# AICat_V1_4.net
KiCad netlist of a schematic drawn in Altium Designer
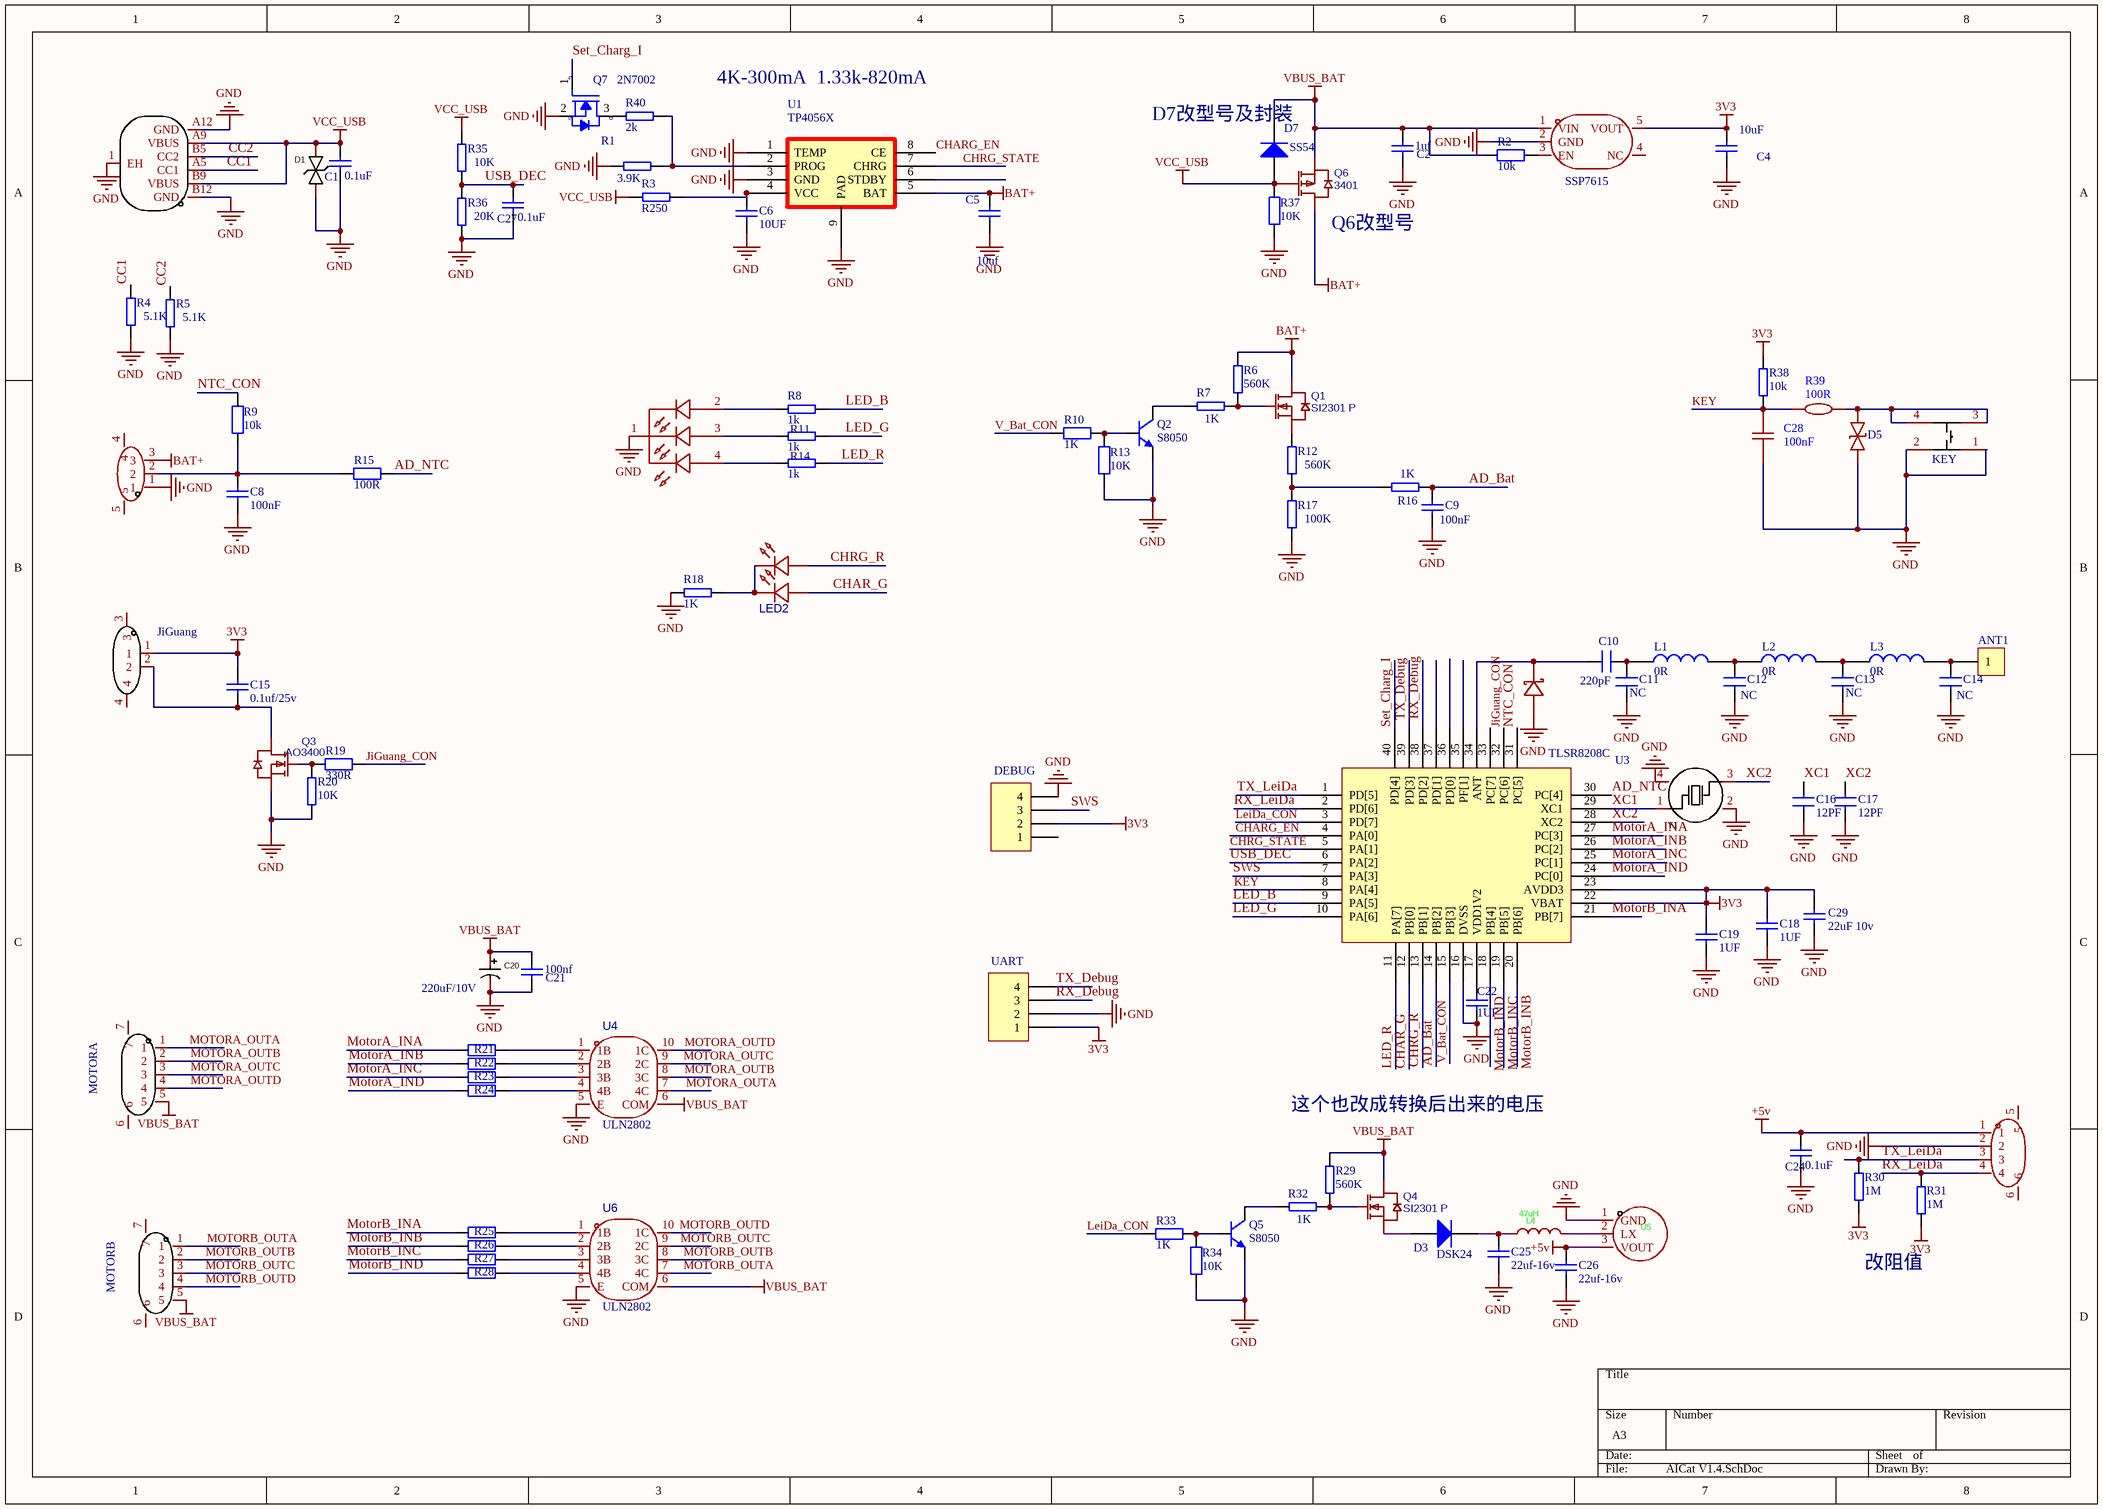
[diagram p0: AICat V1.4.SchDoc]

(export (version "E")
  (design (tool "Eeschema 10.0.6"))
  (components
    (comp (ref "ANT1")
      (value "~")
      (footprint "tp")
      (description "Connector")
      (libsource (lib "*") (part "CON1"))
    )
    (comp (ref "BAT1")
      (value "BX-PH2.0-3PWT")
      (footprint "HDR-TH_3P-P2.50_ZX-XH2.54-3PWZ")
      (libsource (lib "altium-import") (part "root_2_BX-PH2.0-3PWT_"))
    )
    (comp (ref "C1")
      (value "0.1uF")
      (footprint "0603_C")
      (description "Capacitor")
      (fields (field (name "PUBLISHER") "Altium Limited"))
      (libsource (lib "*") (part "Cap"))
    )
    (comp (ref "C2")
      (value "1uf")
      (footprint "0603_C")
      (description "无极电容")
      (libsource (lib "电容电阻电感保险") (part "Cap1"))
    )
    (comp (ref "C4")
      (value "10uF")
      (footprint "0603_C")
      (description "Capacitor")
      (fields (field (name "PUBLISHER") "Altium Limited"))
      (libsource (lib "*") (part "Cap"))
    )
    (comp (ref "C5")
      (value "10uf")
      (footprint "0603_C")
      (description "Capacitor")
      (fields (field (name "PUBLISHER") "Altium Limited"))
      (libsource (lib "*") (part "Cap"))
    )
    (comp (ref "C6") (value "10UF") (footprint "0603_c") (libsource (lib "DIY") (part "CAP")))
    (comp (ref "C8") (value "100nF") (footprint "0603_C") (libsource (lib "DIY") (part "CAP")))
    (comp (ref "C9") (value "100nF") (footprint "0603_C") (libsource (lib "DIY") (part "CAP")))
    (comp (ref "C10")
      (value "220pF")
      (footprint "0402_c")
      (description "Capacitor")
      (libsource (lib "*") (part "CAP"))
    )
    (comp (ref "C11")
      (value "NC")
      (footprint "0402_C")
      (description "Capacitor")
      (libsource (lib "*") (part "CAP"))
    )
    (comp (ref "C12")
      (value "NC")
      (footprint "0402_C")
      (description "Capacitor")
      (libsource (lib "*") (part "CAP"))
    )
    (comp (ref "C13")
      (value "NC")
      (footprint "0402_C")
      (description "Capacitor")
      (libsource (lib "*") (part "CAP"))
    )
    (comp (ref "C14")
      (value "NC")
      (footprint "0402_C")
      (description "Capacitor")
      (libsource (lib "*") (part "CAP"))
    )
    (comp (ref "C15")
      (value "0.1uf/25v")
      (footprint "0603_C")
      (description "Capacitor")
      (fields (field (name "PUBLISHER") "Altium Limited"))
      (libsource (lib "*") (part "Cap"))
    )
    (comp (ref "C16")
      (value "12PF")
      (footprint "0603_c")
      (description "Capacitor")
      (libsource (lib "*") (part "CAP"))
    )
    (comp (ref "C17")
      (value "12PF")
      (footprint "0603_c")
      (description "Capacitor")
      (libsource (lib "*") (part "CAP"))
    )
    (comp (ref "C18") (value "1UF") (footprint "0603_c") (libsource (lib "DIY") (part "CAP")))
    (comp (ref "C19") (value "1UF") (footprint "0603_c") (libsource (lib "DIY") (part "CAP")))
    (comp (ref "C20")
      (value "220uF/10V")
      (footprint "SMD 6.3*5.4 电解")
      (fields (field (name "MANUFACTURER PART") "RVT1A221M0605"))
      (libsource (lib "altium-import") (part "root_0_RVT1A221M0605_C72494_"))
    )
    (comp (ref "C21")
      (value "100nf")
      (footprint "0603_C")
      (description "无极电容")
      (libsource (lib "电容电阻电感保险") (part "Cap1"))
    )
    (comp (ref "C22") (value "1UF") (footprint "0603_c") (libsource (lib "DIY") (part "CAP")))
    (comp (ref "C24")
      (value "0.1uF")
      (footprint "0603_C")
      (description "Capacitor")
      (fields (field (name "PUBLISHER") "Altium Limited"))
      (libsource (lib "*") (part "Cap"))
    )
    (comp (ref "C25")
      (value "22uf-16v")
      (footprint "0805_c")
      (description "无极电容")
      (libsource (lib "电容电阻电感保险") (part "Cap1"))
    )
    (comp (ref "C26")
      (value "22uf-16v")
      (footprint "0805_c")
      (description "无极电容")
      (libsource (lib "电容电阻电感保险") (part "Cap1"))
    )
    (comp (ref "C27")
      (value "0.1uF")
      (footprint "0603_C")
      (description "Capacitor")
      (fields (field (name "PUBLISHER") "Altium Limited"))
      (libsource (lib "*") (part "Cap"))
    )
    (comp (ref "C28")
      (value "100nF")
      (footprint "0603_c")
      (libsource (lib "altium-import") (part "root_1_CAP_0603_"))
    )
    (comp (ref "C29")
      (value "22uF 10v")
      (footprint "0603_C")
      (description "Capacitor")
      (fields (field (name "PUBLISHER") "Altium Limited"))
      (libsource (lib "*") (part "Cap"))
    )
    (comp (ref "CN1")
      (value "JiGuang")
      (footprint "CONN-SMD_2P-P1.25-LT")
      (fields (field (name "MANUFACTURER PART") "HC-1.25-2PLT"))
      (libsource (lib "altium-import") (part "root_0_mirrored_HC-1.25-2PLT_"))
    )
    (comp (ref "CN2")
      (value "HC-1.25-4PLT")
      (footprint "CONN-SMD_4P-P1.25_LT")
      (libsource (lib "altium-import") (part "root_0_HC-1.25-4PLT_"))
    )
    (comp (ref "D1")
      (value "SMF5.0CA_C726939")
      (footprint "SOD-123 双向")
      (fields (field (name "MANUFACTURER PART") "SMF5.0CA"))
      (libsource (lib "altium-import") (part "root_1_SMF5.0CA_C726939_"))
    )
    (comp (ref "D2")
      (value "SE6V3LHN102T 6.3v单向")
      (footprint "0402-D")
      (libsource (lib "altium-import") (part "root_3_TPNSR05F20NXT5G_"))
    )
    (comp (ref "D3")
      (value "DSK24")
      (footprint "SOD-123FL")
      (description "High Conductance Fast Diode")
      (fields (field (name "PUBLISHER") "Altium Limited"))
      (libsource (lib "Miscellaneous Devices") (part "Diode 1N4148"))
    )
    (comp (ref "D5")
      (value "~")
      (footprint "SOD-523_L1.2-W0.8-LS1.6-RD")
      (fields (field (name "MANUFACTURER PART") "LESD5Z5.0CT1G"))
      (libsource (lib "altium-import") (part "root_1_LESD5Z5.0CT1G_"))
    )
    (comp (ref "D7")
      (value "SS54")
      (footprint "SMA")
      (description "High Conductance Fast Diode")
      (fields (field (name "PUBLISHER") "Altium Limited"))
      (libsource (lib "Miscellaneous Devices") (part "Diode 1N4148"))
    )
    (comp (ref "J1")
      (value "MOTORA")
      (footprint "CONN-SMD_1.25-5PLT")
      (fields (field (name "MANUFACTURER PART") "HC-1.25-5PLT"))
      (libsource (lib "altium-import") (part "root_0_mirrored_HC-1.25-5PLT_"))
    )
    (comp (ref "J2")
      (value "MOTORB")
      (footprint "CONN-SMD_1.25-5PLT")
      (fields (field (name "MANUFACTURER PART") "HC-1.25-5PLT"))
      (libsource (lib "altium-import") (part "root_0_mirrored_HC-1.25-5PLT_"))
    )
    (comp (ref "K1")
      (value "KEY")
      (footprint "KEY_SMD_4P")
      (fields (field (name "MANUFACTURER PART") "TS-1002S-05026C"))
      (libsource (lib "altium-import") (part "root_2_TS-1002S-05026C_"))
    )
    (comp (ref "L1") (value "0R") (footprint "0402_R") (libsource (lib "*") (part "INDUCTOR")))
    (comp (ref "L2") (value "0R") (footprint "0402_R") (libsource (lib "*") (part "INDUCTOR")))
    (comp (ref "L3") (value "0R") (footprint "0402_R") (libsource (lib "*") (part "INDUCTOR")))
    (comp (ref "L4")
      (value "47uH")
      (footprint "IND-SMD_L3.5-W3.0_CD31")
      (fields (field (name "MANUFACTURER PART") "CD31-470M 47UH"))
      (libsource (lib "altium-import") (part "root_0_CD31-470M 47UH_"))
    )
    (comp (ref "LED1")
      (value "XL-A3528RGBC-BM")
      (footprint "LED-ARRAY-SMD_4P-L3.2-W2.8-LS3.5-BL_XL-A3528RGBC-BM")
      (libsource (lib "altium-import") (part "root_2_XL-A3528RGBC-BM_"))
    )
    (comp (ref "LED2")
      (value "*")
      (footprint "LED-SMD_4P-L3.2-W1.6-TL_XL-3216SURUGC")
      (libsource (lib "altium-import") (part "root_0_TJ-S2012SW8TCGLC2R2G-A5_"))
    )
    (comp (ref "P1")
      (value "DEBUG")
      (footprint "SIP4-2.54")
      (description "Header, 4-Pin")
      (fields (field (name "PUBLISHER") "Altium Limited"))
      (libsource (lib "Miscellaneous Connectors") (part "Header 4"))
    )
    (comp (ref "P2")
      (value "UART")
      (footprint "SIP4-2.54")
      (description "Header, 4-Pin")
      (fields (field (name "PUBLISHER") "Altium Limited"))
      (libsource (lib "Miscellaneous Connectors") (part "Header 4"))
    )
    (comp (ref "Q1")
      (value "SI2301 P")
      (footprint "SOT-23")
      (fields
        (field (name "BOM_SUPPLIER PART") "C2890442")
        (field (name "BOM_MANUFACTURER PART") "JMTL3400A")
        (field (name "CONTRIBUTOR") "LCSC")
      )
      (libsource (lib "altium-import") (part "root_0_JMTL3400A_"))
    )
    (comp (ref "Q2")
      (value "S8050")
      (footprint "SOT-23(SOT-23-3)")
      (description "NPN三极管")
      (libsource (lib "二三极管mos可控硅") (part "NPN_sot23"))
    )
    (comp (ref "Q3")
      (value "AO3400")
      (footprint "SOT-23")
      (fields
        (field (name "BOM_SUPPLIER PART") "C2890442")
        (field (name "BOM_MANUFACTURER PART") "JMTL3400A")
        (field (name "CONTRIBUTOR") "LCSC")
      )
      (libsource (lib "altium-import") (part "root_0_mirrored_JMTL3400A_"))
    )
    (comp (ref "Q4")
      (value "SI2301 P")
      (footprint "SOT-23")
      (fields
        (field (name "BOM_SUPPLIER PART") "C2890442")
        (field (name "BOM_MANUFACTURER PART") "JMTL3400A")
        (field (name "CONTRIBUTOR") "LCSC")
      )
      (libsource (lib "altium-import") (part "root_0_JMTL3400A_"))
    )
    (comp (ref "Q5")
      (value "S8050")
      (footprint "SOT-23(SOT-23-3)")
      (description "NPN三极管")
      (libsource (lib "二三极管mos可控硅") (part "NPN_sot23"))
    )
    (comp (ref "Q6")
      (value "3401")
      (footprint "SOT-23")
      (fields (field (name "BOM_MANUFACTURER PART") "CJ3401") (field (name "BOM_SUPPLIER PART") "C13799"))
      (libsource (lib "altium-import") (part "root_2_mirrored_CJ3401_"))
    )
    (comp (ref "Q7") (value "2N7002") (footprint "SOT-23") (libsource (lib "*") (part "AO3400_SOT23")))
    (comp (ref "R1") (value "3.9K") (footprint "0603_R") (libsource (lib "DIY") (part "RES")))
    (comp (ref "R2")
      (value "10k")
      (footprint "0603_R")
      (description "Resistor")
      (fields (field (name "PUBLISHER") "Altium Limited"))
      (libsource (lib "") (part "Res2_2"))
    )
    (comp (ref "R3") (value "R250") (footprint "1206_R") (libsource (lib "DIY") (part "RES")))
    (comp (ref "R4") (value "5.1K") (footprint "0603_R") (libsource (lib "DIY") (part "RES")))
    (comp (ref "R5") (value "5.1K") (footprint "0603_R") (libsource (lib "DIY") (part "RES")))
    (comp (ref "R6") (value "560K") (footprint "0603_R") (libsource (lib "*") (part "RES")))
    (comp (ref "R7") (value "1K") (footprint "0603_R") (libsource (lib "") (part "RES_1")))
    (comp (ref "R8") (value "1k") (footprint "0603_R") (libsource (lib "DIY") (part "RES")))
    (comp (ref "R9")
      (value "10k")
      (footprint "0603_R")
      (description "Resistor")
      (fields (field (name "PUBLISHER") "Altium Limited"))
      (libsource (lib "") (part "Res2_3"))
    )
    (comp (ref "R10")
      (value "1K")
      (footprint "0603_r")
      (description "Resistor")
      (fields (field (name "PUBLISHER") "Altium Limited"))
      (libsource (lib "") (part "Res2_4"))
    )
    (comp (ref "R11") (value "1k") (footprint "0603_R") (libsource (lib "DIY") (part "RES")))
    (comp (ref "R12") (value "560K") (footprint "0603_R") (libsource (lib "DIY") (part "RES")))
    (comp (ref "R13")
      (value "10K")
      (footprint "0603_r")
      (description "Resistor")
      (fields (field (name "PUBLISHER") "Altium Limited"))
      (libsource (lib "") (part "Res2_2"))
    )
    (comp (ref "R14") (value "1k") (footprint "0603_R") (libsource (lib "DIY") (part "RES")))
    (comp (ref "R15")
      (value "100R")
      (footprint "0603_R")
      (description "Resistor")
      (fields (field (name "PUBLISHER") "Altium Limited"))
      (libsource (lib "") (part "Res2_1"))
    )
    (comp (ref "R16") (value "1K") (footprint "0603_R") (libsource (lib "DIY") (part "RES")))
    (comp (ref "R17") (value "100K") (footprint "0603_R") (libsource (lib "DIY") (part "RES")))
    (comp (ref "R18") (value "1K") (footprint "0603_R") (libsource (lib "DIY") (part "RES")))
    (comp (ref "R19")
      (value "330R")
      (footprint "0603_R")
      (description "Resistor")
      (fields (field (name "PUBLISHER") "Altium Limited"))
      (libsource (lib "") (part "Res2_3"))
    )
    (comp (ref "R20") (value "10K") (footprint "0603_R") (libsource (lib "DIY") (part "RES")))
    (comp (ref "R21")
      (value "330R")
      (footprint "0603_R")
      (description "Resistor")
      (fields (field (name "PUBLISHER") "Altium Limited"))
      (libsource (lib "*") (part "Res2"))
    )
    (comp (ref "R22")
      (value "330R")
      (footprint "0603_R")
      (description "Resistor")
      (fields (field (name "PUBLISHER") "Altium Limited"))
      (libsource (lib "*") (part "Res2"))
    )
    (comp (ref "R23")
      (value "330R")
      (footprint "0603_R")
      (description "Resistor")
      (fields (field (name "PUBLISHER") "Altium Limited"))
      (libsource (lib "*") (part "Res2"))
    )
    (comp (ref "R24")
      (value "330R")
      (footprint "0603_R")
      (description "Resistor")
      (fields (field (name "PUBLISHER") "Altium Limited"))
      (libsource (lib "*") (part "Res2"))
    )
    (comp (ref "R25")
      (value "330R")
      (footprint "0603_R")
      (description "Resistor")
      (fields (field (name "PUBLISHER") "Altium Limited"))
      (libsource (lib "*") (part "Res2"))
    )
    (comp (ref "R26")
      (value "330R")
      (footprint "0603_R")
      (description "Resistor")
      (fields (field (name "PUBLISHER") "Altium Limited"))
      (libsource (lib "*") (part "Res2"))
    )
    (comp (ref "R27")
      (value "330R")
      (footprint "0603_R")
      (description "Resistor")
      (fields (field (name "PUBLISHER") "Altium Limited"))
      (libsource (lib "*") (part "Res2"))
    )
    (comp (ref "R28")
      (value "330R")
      (footprint "0603_R")
      (description "Resistor")
      (fields (field (name "PUBLISHER") "Altium Limited"))
      (libsource (lib "*") (part "Res2"))
    )
    (comp (ref "R29") (value "560K") (footprint "0603_R") (libsource (lib "*") (part "RES")))
    (comp (ref "R30") (value "1M") (footprint "0603_R") (libsource (lib "*") (part "RES")))
    (comp (ref "R31") (value "1M") (footprint "0603_R") (libsource (lib "*") (part "RES")))
    (comp (ref "R32") (value "1K") (footprint "0603_R") (libsource (lib "") (part "RES_1")))
    (comp (ref "R33")
      (value "1K")
      (footprint "0603_r")
      (description "Resistor")
      (fields (field (name "PUBLISHER") "Altium Limited"))
      (libsource (lib "") (part "Res2_4"))
    )
    (comp (ref "R34")
      (value "10K")
      (footprint "0603_r")
      (description "Resistor")
      (fields (field (name "PUBLISHER") "Altium Limited"))
      (libsource (lib "") (part "Res2_2"))
    )
    (comp (ref "R35") (value "10K") (footprint "0603_R") (libsource (lib "DIY") (part "RES")))
    (comp (ref "R36") (value "20K") (footprint "0603_R") (libsource (lib "DIY") (part "RES")))
    (comp (ref "R37")
      (value "10K")
      (footprint "0603_R")
      (description "Resistor")
      (fields (field (name "PUBLISHER") "Altium Limited"))
      (libsource (lib "") (part "Res2_3"))
    )
    (comp (ref "R38") (value "10k") (footprint "0603_R") (libsource (lib "DIY") (part "RES")))
    (comp (ref "R39")
      (value "100R")
      (footprint "0603_r")
      (libsource (lib "altium-import") (part "root_2_Res_0603_"))
    )
    (comp (ref "R40") (value "2k") (footprint "0603_R") (libsource (lib "DIY") (part "RES")))
    (comp (ref "U1")
      (value "TP4056X")
      (footprint "SOP8-9")
      (description "TP4056")
      (libsource (lib "芯片") (part "TP4056"))
    )
    (comp (ref "U2")
      (value "SSP7615")
      (footprint "SOT-23-5")
      (libsource (lib "altium-import") (part "root_0_SSP7615-33M5R_"))
    )
    (comp (ref "U3")
      (value "TLSR8208C")
      (footprint "QFN-40_L5.0-W5.0-P0.40-BL-EP3.7")
      (libsource (lib "MyLib") (part "TLSR8208C"))
    )
    (comp (ref "U4")
      (value "ULN2802")
      (footprint "ESSOP-10")
      (libsource (lib "altium-import") (part "root_0_ULN2802_C2828555_"))
    )
    (comp (ref "U5")
      (value "HE9116A50NR")
      (footprint "SOT-23")
      (libsource (lib "altium-import") (part "root_0_HE9116A50NR_"))
    )
    (comp (ref "U6")
      (value "ULN2802")
      (footprint "ESSOP-10")
      (libsource (lib "altium-import") (part "root_0_ULN2802_C2828555_"))
    )
    (comp (ref "USB1")
      (value "TYPE-C 6P")
      (footprint "TPYE-C-6")
      (fields (field (name "MANUFACTURER PART") "TYPE-C 6P LTH6.5"))
      (libsource (lib "altium-import") (part "root_2_TYPE-C 6P LTH6.5_"))
    )
    (comp (ref "Y1")
      (value "24MHz +-20PPM")
      (footprint "CRYSTAL-SMD_4P-L3.2-W2.5")
      (fields (field (name "MANUFACTURER PART") "TAXM13.56M4RLBCCT2T"))
      (libsource (lib "altium-import") (part "root_0_TAXM13.56M4RLBCCT2T_"))
    )
  )
  (nets
    (net (code "1") (name "+5v") (class "Default")
      (node (ref "C24") (pin "2") (pinfunction "2_2") (pintype "passive"))
      (node (ref "C26") (pin "1") (pinfunction "1_1") (pintype "passive"))
      (node (ref "CN2") (pin "1") (pinfunction "1_1") (pintype "passive"))
      (node (ref "U5") (pin "3") (pinfunction "VOUT_3") (pintype "passive"))
    )
    (net (code "2") (name "/AD_Bat") (class "Default")
      (node (ref "C9") (pin "2") (pintype "passive"))
      (node (ref "R16") (pin "1") (pinfunction "1_1") (pintype "passive"))
      (node (ref "U3") (pin "14") (pinfunction "PB[2]_14") (pintype "passive"))
    )
    (net (code "3") (name "/AD_NTC") (class "Default")
      (node (ref "R15") (pin "1") (pinfunction "1_1") (pintype "passive"))
      (node (ref "U3") (pin "30") (pinfunction "PC[4]_30") (pintype "passive"))
    )
    (net (code "4") (name "/CC1") (class "Default")
      (node (ref "R4") (pin "1") (pinfunction "1_1") (pintype "passive"))
      (node (ref "USB1") (pin "A5") (pinfunction "CC1_A5") (pintype "passive"))
    )
    (net (code "5") (name "/CC2") (class "Default")
      (node (ref "R5") (pin "1") (pinfunction "1_1") (pintype "passive"))
      (node (ref "USB1") (pin "B5") (pinfunction "CC2_B5") (pintype "passive"))
    )
    (net (code "6") (name "/CHARG_EN") (class "Default")
      (node (ref "U1") (pin "8") (pinfunction "CE_8") (pintype "passive"))
      (node (ref "U3") (pin "4") (pinfunction "PA[0]_4") (pintype "passive"))
    )
    (net (code "7") (name "/CHAR_G") (class "Default")
      (node (ref "LED2") (pin "3") (pinfunction "A_3") (pintype "passive"))
      (node (ref "U3") (pin "12") (pinfunction "PB[0]_12") (pintype "passive"))
    )
    (net (code "8") (name "/CHRG_R") (class "Default")
      (node (ref "LED2") (pin "1") (pinfunction "A_1") (pintype "passive"))
      (node (ref "U3") (pin "13") (pinfunction "PB[1]_13") (pintype "passive"))
    )
    (net (code "9") (name "/CHRG_STATE") (class "Default")
      (node (ref "U1") (pin "7") (pinfunction "CHRG_7") (pintype "passive"))
      (node (ref "U3") (pin "5") (pinfunction "PA[1]_5") (pintype "passive"))
    )
    (net (code "10") (name "/JiGuang_CON") (class "Default")
      (node (ref "R19") (pin "2") (pinfunction "2_2") (pintype "passive"))
      (node (ref "U3") (pin "32") (pinfunction "PC[6]_32") (pintype "passive"))
    )
    (net (code "11") (name "/KEY") (class "Default")
      (node (ref "C28") (pin "2") (pinfunction "2_2") (pintype "passive"))
      (node (ref "R38") (pin "1") (pinfunction "1_1") (pintype "passive"))
      (node (ref "R39") (pin "2") (pinfunction "2_2") (pintype "passive"))
      (node (ref "U3") (pin "8") (pinfunction "PA[4]_8") (pintype "passive"))
    )
    (net (code "12") (name "/LED_B") (class "Default")
      (node (ref "R8") (pin "2") (pinfunction "2_2") (pintype "passive"))
      (node (ref "U3") (pin "9") (pinfunction "PA[5]_9") (pintype "passive"))
    )
    (net (code "13") (name "/LED_G") (class "Default")
      (node (ref "R11") (pin "2") (pinfunction "2_2") (pintype "passive"))
      (node (ref "U3") (pin "10") (pinfunction "PA[6]_10") (pintype "passive"))
    )
    (net (code "14") (name "/LED_R") (class "Default")
      (node (ref "R14") (pin "2") (pinfunction "2_2") (pintype "passive"))
      (node (ref "U3") (pin "11") (pinfunction "PA[7]_11") (pintype "passive"))
    )
    (net (code "15") (name "/LeiDa_CON") (class "Default")
      (node (ref "R33") (pin "2") (pinfunction "2_2") (pintype "passive"))
      (node (ref "U3") (pin "3") (pinfunction "PD[7]_3") (pintype "passive"))
    )
    (net (code "16") (name "/MOTORA_OUTA") (class "Default")
      (node (ref "J1") (pin "1") (pinfunction "1_1") (pintype "passive"))
      (node (ref "U4") (pin "7") (pinfunction "4C_7") (pintype "passive"))
    )
    (net (code "17") (name "/MOTORA_OUTB") (class "Default")
      (node (ref "J1") (pin "2") (pinfunction "2_2") (pintype "passive"))
      (node (ref "U4") (pin "8") (pinfunction "3C_8") (pintype "passive"))
    )
    (net (code "18") (name "/MOTORA_OUTC") (class "Default")
      (node (ref "J1") (pin "3") (pinfunction "3_3") (pintype "passive"))
      (node (ref "U4") (pin "9") (pinfunction "2C_9") (pintype "passive"))
    )
    (net (code "19") (name "/MOTORA_OUTD") (class "Default")
      (node (ref "J1") (pin "4") (pinfunction "4_4") (pintype "passive"))
      (node (ref "U4") (pin "10") (pinfunction "1C_10") (pintype "passive"))
    )
    (net (code "20") (name "/MOTORB_OUTA") (class "Default")
      (node (ref "J2") (pin "1") (pinfunction "1_1") (pintype "passive"))
      (node (ref "U6") (pin "7") (pinfunction "4C_7") (pintype "passive"))
    )
    (net (code "21") (name "/MOTORB_OUTB") (class "Default")
      (node (ref "J2") (pin "2") (pinfunction "2_2") (pintype "passive"))
      (node (ref "U6") (pin "8") (pinfunction "3C_8") (pintype "passive"))
    )
    (net (code "22") (name "/MOTORB_OUTC") (class "Default")
      (node (ref "J2") (pin "3") (pinfunction "3_3") (pintype "passive"))
      (node (ref "U6") (pin "9") (pinfunction "2C_9") (pintype "passive"))
    )
    (net (code "23") (name "/MOTORB_OUTD") (class "Default")
      (node (ref "J2") (pin "4") (pinfunction "4_4") (pintype "passive"))
      (node (ref "U6") (pin "10") (pinfunction "1C_10") (pintype "passive"))
    )
    (net (code "24") (name "/MotorA_INA") (class "Default")
      (node (ref "R21") (pin "2") (pinfunction "2_2") (pintype "passive"))
      (node (ref "U3") (pin "27") (pinfunction "PC[3]_27") (pintype "passive"))
    )
    (net (code "25") (name "/MotorA_INB") (class "Default")
      (node (ref "R22") (pin "2") (pinfunction "2_2") (pintype "passive"))
      (node (ref "U3") (pin "26") (pinfunction "PC[2]_26") (pintype "passive"))
    )
    (net (code "26") (name "/MotorA_INC") (class "Default")
      (node (ref "R23") (pin "2") (pinfunction "2_2") (pintype "passive"))
      (node (ref "U3") (pin "25") (pinfunction "PC[1]_25") (pintype "passive"))
    )
    (net (code "27") (name "/MotorA_IND") (class "Default")
      (node (ref "R24") (pin "2") (pinfunction "2_2") (pintype "passive"))
      (node (ref "U3") (pin "24") (pinfunction "PC[0]_24") (pintype "passive"))
    )
    (net (code "28") (name "/MotorB_INA") (class "Default")
      (node (ref "R25") (pin "2") (pinfunction "2_2") (pintype "passive"))
      (node (ref "U3") (pin "21") (pinfunction "PB[7]_21") (pintype "passive"))
    )
    (net (code "29") (name "/MotorB_INB") (class "Default")
      (node (ref "R26") (pin "2") (pinfunction "2_2") (pintype "passive"))
      (node (ref "U3") (pin "20") (pinfunction "PB[6]_20") (pintype "passive"))
    )
    (net (code "30") (name "/MotorB_INC") (class "Default")
      (node (ref "R27") (pin "2") (pinfunction "2_2") (pintype "passive"))
      (node (ref "U3") (pin "19") (pinfunction "PB[5]_19") (pintype "passive"))
    )
    (net (code "31") (name "/MotorB_IND") (class "Default")
      (node (ref "R28") (pin "2") (pinfunction "2_2") (pintype "passive"))
      (node (ref "U3") (pin "18") (pinfunction "PB[4]_18") (pintype "passive"))
    )
    (net (code "32") (name "/NTC_CON") (class "Default")
      (node (ref "R9") (pin "2") (pinfunction "2_2") (pintype "passive"))
      (node (ref "U3") (pin "31") (pinfunction "PC[5]_31") (pintype "passive"))
    )
    (net (code "33") (name "/RX_Debug") (class "Default")
      (node (ref "P2") (pin "3") (pinfunction "3_3") (pintype "passive"))
      (node (ref "U3") (pin "38") (pinfunction "PD[2]_38") (pintype "passive"))
    )
    (net (code "34") (name "/RX_LeiDa") (class "Default")
      (node (ref "CN2") (pin "4") (pinfunction "4_4") (pintype "passive"))
      (node (ref "R31") (pin "1") (pintype "passive"))
      (node (ref "U3") (pin "2") (pinfunction "PD[6]_2") (pintype "passive"))
    )
    (net (code "35") (name "/SWS") (class "Default")
      (node (ref "P1") (pin "3") (pinfunction "3_3") (pintype "passive"))
      (node (ref "U3") (pin "7") (pinfunction "PA[3]_7") (pintype "passive"))
    )
    (net (code "36") (name "/Set_Charg_I") (class "Default")
      (node (ref "Q7") (pin "1") (pinfunction "GATE_1") (pintype "passive"))
      (node (ref "U3") (pin "40") (pinfunction "PD[4]_40") (pintype "passive"))
    )
    (net (code "37") (name "/TX_Debug") (class "Default")
      (node (ref "P2") (pin "4") (pinfunction "4_4") (pintype "passive"))
      (node (ref "U3") (pin "39") (pinfunction "PD[3]_39") (pintype "passive"))
    )
    (net (code "38") (name "/TX_LeiDa") (class "Default")
      (node (ref "CN2") (pin "3") (pinfunction "3_3") (pintype "passive"))
      (node (ref "R30") (pin "1") (pintype "passive"))
      (node (ref "U3") (pin "1") (pinfunction "PD[5]_1") (pintype "passive"))
    )
    (net (code "39") (name "/USB_DEC") (class "Default")
      (node (ref "C27") (pin "2") (pinfunction "2_2") (pintype "passive"))
      (node (ref "R35") (pin "2") (pinfunction "2_2") (pintype "passive"))
      (node (ref "R36") (pin "1") (pinfunction "1_1") (pintype "passive"))
      (node (ref "U3") (pin "6") (pinfunction "PA[2]_6") (pintype "passive"))
    )
    (net (code "40") (name "/V_Bat_CON") (class "Default")
      (node (ref "R10") (pin "2") (pinfunction "2_2") (pintype "passive"))
      (node (ref "U3") (pin "15") (pinfunction "PB[3]_15") (pintype "passive"))
    )
    (net (code "41") (name "/XC1") (class "Default")
      (node (ref "C16") (pin "2") (pinfunction "2_2") (pintype "passive"))
      (node (ref "U3") (pin "29") (pinfunction "XC1_29") (pintype "passive"))
      (node (ref "Y1") (pin "1") (pinfunction "OSC1_1") (pintype "passive"))
    )
    (net (code "42") (name "/XC2") (class "Default")
      (node (ref "C17") (pin "2") (pinfunction "2_2") (pintype "passive"))
      (node (ref "U3") (pin "28") (pinfunction "XC2_28") (pintype "passive"))
      (node (ref "Y1") (pin "3") (pinfunction "OSC2_3") (pintype "passive"))
    )
    (net (code "43") (name "3V3") (class "Default")
      (node (ref "C15") (pin "2") (pinfunction "2_2") (pintype "passive"))
      (node (ref "C18") (pin "1") (pintype "passive"))
      (node (ref "C19") (pin "1") (pintype "passive"))
      (node (ref "C29") (pin "2") (pinfunction "2_2") (pintype "passive"))
      (node (ref "C4") (pin "2") (pinfunction "2_2") (pintype "passive"))
      (node (ref "CN1") (pin "1") (pinfunction "1_1") (pintype "passive"))
      (node (ref "P1") (pin "2") (pinfunction "2_2") (pintype "passive"))
      (node (ref "P2") (pin "1") (pinfunction "1_1") (pintype "passive"))
      (node (ref "R30") (pin "2") (pintype "passive"))
      (node (ref "R31") (pin "2") (pintype "passive"))
      (node (ref "R38") (pin "2") (pinfunction "2_2") (pintype "passive"))
      (node (ref "U2") (pin "5") (pinfunction "VOUT_5") (pintype "passive"))
      (node (ref "U3") (pin "22") (pinfunction "VBAT_22") (pintype "passive"))
      (node (ref "U3") (pin "23") (pinfunction "AVDD3_23") (pintype "passive"))
    )
    (net (code "44") (name "BAT+") (class "Default")
      (node (ref "BAT1") (pin "3") (pinfunction "3_3") (pintype "passive"))
      (node (ref "C5") (pin "1") (pinfunction "1_1") (pintype "passive"))
      (node (ref "Q1") (pin "2") (pinfunction "D_2") (pintype "passive"))
      (node (ref "Q6") (pin "3") (pinfunction "D_3") (pintype "passive"))
      (node (ref "R6") (pin "1") (pintype "passive"))
      (node (ref "U1") (pin "5") (pinfunction "BAT_5") (pintype "passive"))
    )
    (net (code "45") (name "GND") (class "Default")
      (node (ref "BAT1") (pin "1") (pinfunction "1_1") (pintype "passive"))
      (node (ref "C1") (pin "1") (pinfunction "1_1") (pintype "passive"))
      (node (ref "C11") (pin "1") (pinfunction "1_1") (pintype "passive"))
      (node (ref "C12") (pin "1") (pinfunction "1_1") (pintype "passive"))
      (node (ref "C13") (pin "1") (pinfunction "1_1") (pintype "passive"))
      (node (ref "C14") (pin "1") (pinfunction "1_1") (pintype "passive"))
      (node (ref "C16") (pin "1") (pinfunction "1_1") (pintype "passive"))
      (node (ref "C17") (pin "1") (pinfunction "1_1") (pintype "passive"))
      (node (ref "C18") (pin "2") (pintype "passive"))
      (node (ref "C19") (pin "2") (pintype "passive"))
      (node (ref "C2") (pin "1") (pinfunction "1_1") (pintype "passive"))
      (node (ref "C20") (pin "2") (pinfunction "2_2") (pintype "passive"))
      (node (ref "C21") (pin "1") (pinfunction "1_1") (pintype "passive"))
      (node (ref "C22") (pin "1") (pintype "passive"))
      (node (ref "C24") (pin "1") (pinfunction "1_1") (pintype "passive"))
      (node (ref "C25") (pin "2") (pinfunction "2_2") (pintype "passive"))
      (node (ref "C26") (pin "2") (pinfunction "2_2") (pintype "passive"))
      (node (ref "C27") (pin "1") (pinfunction "1_1") (pintype "passive"))
      (node (ref "C28") (pin "1") (pinfunction "1_1") (pintype "passive"))
      (node (ref "C29") (pin "1") (pinfunction "1_1") (pintype "passive"))
      (node (ref "C4") (pin "1") (pinfunction "1_1") (pintype "passive"))
      (node (ref "C5") (pin "2") (pinfunction "2_2") (pintype "passive"))
      (node (ref "C6") (pin "1") (pintype "passive"))
      (node (ref "C8") (pin "2") (pintype "passive"))
      (node (ref "C9") (pin "1") (pintype "passive"))
      (node (ref "CN2") (pin "2") (pinfunction "2_2") (pintype "passive"))
      (node (ref "D1") (pin "1") (pinfunction "1_1") (pintype "passive"))
      (node (ref "D2") (pin "2") (pinfunction "A_2") (pintype "passive"))
      (node (ref "D5") (pin "1") (pinfunction "1_1") (pintype "passive"))
      (node (ref "K1") (pin "1") (pinfunction "1_1") (pintype "passive"))
      (node (ref "K1") (pin "2") (pinfunction "2_2") (pintype "passive"))
      (node (ref "LED1") (pin "1") (pinfunction "1_1") (pintype "passive"))
      (node (ref "P1") (pin "4") (pinfunction "4_4") (pintype "passive"))
      (node (ref "P2") (pin "2") (pinfunction "2_2") (pintype "passive"))
      (node (ref "Q2") (pin "2") (pinfunction "E_2") (pintype "passive"))
      (node (ref "Q3") (pin "2") (pinfunction "S_2") (pintype "passive"))
      (node (ref "Q5") (pin "2") (pinfunction "E_2") (pintype "passive"))
      (node (ref "Q7") (pin "2") (pinfunction "SOURCE_2") (pintype "passive"))
      (node (ref "R1") (pin "1") (pinfunction "1_1") (pintype "passive"))
      (node (ref "R13") (pin "1") (pinfunction "1_1") (pintype "passive"))
      (node (ref "R17") (pin "2") (pinfunction "2_2") (pintype "passive"))
      (node (ref "R18") (pin "1") (pinfunction "1_1") (pintype "passive"))
      (node (ref "R20") (pin "1") (pinfunction "1_1") (pintype "passive"))
      (node (ref "R34") (pin "1") (pinfunction "1_1") (pintype "passive"))
      (node (ref "R36") (pin "2") (pinfunction "2_2") (pintype "passive"))
      (node (ref "R37") (pin "1") (pinfunction "1_1") (pintype "passive"))
      (node (ref "R4") (pin "2") (pinfunction "2_2") (pintype "passive"))
      (node (ref "R5") (pin "2") (pinfunction "2_2") (pintype "passive"))
      (node (ref "U1") (pin "1") (pinfunction "TEMP_1") (pintype "passive"))
      (node (ref "U1") (pin "3") (pinfunction "GND_3") (pintype "passive"))
      (node (ref "U1") (pin "9") (pinfunction "PAD_9") (pintype "passive"))
      (node (ref "U2") (pin "2") (pinfunction "GND_2") (pintype "passive"))
      (node (ref "U3") (pin "16") (pinfunction "DVSS_16") (pintype "passive"))
      (node (ref "U4") (pin "5") (pinfunction "E_5") (pintype "passive"))
      (node (ref "U5") (pin "1") (pinfunction "GND_1") (pintype "passive"))
      (node (ref "U6") (pin "5") (pinfunction "E_5") (pintype "passive"))
      (node (ref "USB1") (pin "1") (pinfunction "EH_1") (pintype "passive"))
      (node (ref "USB1") (pin "A12") (pinfunction "GND_A12") (pintype "passive"))
      (node (ref "USB1") (pin "B12") (pinfunction "GND_B12") (pintype "passive"))
      (node (ref "Y1") (pin "2") (pinfunction "GND_2") (pintype "passive"))
      (node (ref "Y1") (pin "4") (pinfunction "GND_4") (pintype "passive"))
    )
    (net (code "46") (name "Net-(ANT1-Pad1)") (class "Default")
      (node (ref "ANT1") (pin "1") (pinfunction "1_1") (pintype "passive"))
      (node (ref "C14") (pin "2") (pinfunction "2_2") (pintype "passive"))
      (node (ref "L3") (pin "2") (pinfunction "2_2") (pintype "passive"))
    )
    (net (code "47") (name "Net-(BAT1-Pad2)") (class "Default")
      (node (ref "BAT1") (pin "2") (pinfunction "2_2") (pintype "passive"))
      (node (ref "C8") (pin "1") (pintype "passive"))
      (node (ref "R15") (pin "2") (pinfunction "2_2") (pintype "passive"))
      (node (ref "R9") (pin "1") (pinfunction "1_1") (pintype "passive"))
    )
    (net (code "48") (name "Net-(C10-Pad2)") (class "Default")
      (node (ref "C10") (pin "2") (pinfunction "2_2") (pintype "passive"))
      (node (ref "C11") (pin "2") (pinfunction "2_2") (pintype "passive"))
      (node (ref "L1") (pin "1") (pinfunction "1_1") (pintype "passive"))
    )
    (net (code "49") (name "Net-(C12-Pad2)") (class "Default")
      (node (ref "C12") (pin "2") (pinfunction "2_2") (pintype "passive"))
      (node (ref "L1") (pin "2") (pinfunction "2_2") (pintype "passive"))
      (node (ref "L2") (pin "1") (pinfunction "1_1") (pintype "passive"))
    )
    (net (code "50") (name "Net-(C13-Pad2)") (class "Default")
      (node (ref "C13") (pin "2") (pinfunction "2_2") (pintype "passive"))
      (node (ref "L2") (pin "2") (pinfunction "2_2") (pintype "passive"))
      (node (ref "L3") (pin "1") (pinfunction "1_1") (pintype "passive"))
    )
    (net (code "51") (name "Net-(D2-C)") (class "Default")
      (node (ref "C10") (pin "1") (pinfunction "1_1") (pintype "passive"))
      (node (ref "D2") (pin "1") (pinfunction "C_1") (pintype "passive"))
      (node (ref "U3") (pin "34") (pinfunction "ANT_34") (pintype "passive"))
    )
    (net (code "52") (name "Net-(D3-A)") (class "Default")
      (node (ref "D3") (pin "1") (pinfunction "A_1") (pintype "passive"))
      (node (ref "Q4") (pin "3") (pinfunction "S_3") (pintype "passive"))
    )
    (net (code "53") (name "Net-(D3-K)") (class "Default")
      (node (ref "C25") (pin "1") (pinfunction "1_1") (pintype "passive"))
      (node (ref "D3") (pin "2") (pinfunction "K_2") (pintype "passive"))
      (node (ref "L4") (pin "1") (pinfunction "1_1") (pintype "passive"))
    )
    (net (code "54") (name "Net-(D5-Pad2)") (class "Default")
      (node (ref "D5") (pin "2") (pinfunction "2_2") (pintype "passive"))
      (node (ref "K1") (pin "3") (pinfunction "3_3") (pintype "passive"))
      (node (ref "K1") (pin "4") (pinfunction "4_4") (pintype "passive"))
      (node (ref "R39") (pin "1") (pinfunction "1_1") (pintype "passive"))
    )
    (net (code "55") (name "Net-(LED1-Pad2)") (class "Default")
      (node (ref "LED1") (pin "2") (pinfunction "2_2") (pintype "passive"))
      (node (ref "R8") (pin "1") (pinfunction "1_1") (pintype "passive"))
    )
    (net (code "56") (name "Net-(LED1-Pad3)") (class "Default")
      (node (ref "LED1") (pin "3") (pinfunction "3_3") (pintype "passive"))
      (node (ref "R11") (pin "1") (pinfunction "1_1") (pintype "passive"))
    )
    (net (code "57") (name "Net-(LED1-Pad4)") (class "Default")
      (node (ref "LED1") (pin "4") (pinfunction "4_4") (pintype "passive"))
      (node (ref "R14") (pin "1") (pinfunction "1_1") (pintype "passive"))
    )
    (net (code "58") (name "Net-(LED2-K-Pad2)") (class "Default")
      (node (ref "LED2") (pin "2") (pinfunction "K_2") (pintype "passive"))
      (node (ref "LED2") (pin "4") (pinfunction "K_4") (pintype "passive"))
      (node (ref "R18") (pin "2") (pinfunction "2_2") (pintype "passive"))
    )
    (net (code "59") (name "Net-(Q1-G)") (class "Default")
      (node (ref "Q1") (pin "1") (pinfunction "G_1") (pintype "passive"))
      (node (ref "R6") (pin "2") (pintype "passive"))
      (node (ref "R7") (pin "1") (pintype "passive"))
    )
    (net (code "60") (name "Net-(Q1-S)") (class "Default")
      (node (ref "Q1") (pin "3") (pinfunction "S_3") (pintype "passive"))
      (node (ref "R12") (pin "1") (pinfunction "1_1") (pintype "passive"))
    )
    (net (code "61") (name "Net-(Q2-B)") (class "Default")
      (node (ref "Q2") (pin "1") (pinfunction "B_1") (pintype "passive"))
      (node (ref "R10") (pin "1") (pinfunction "1_1") (pintype "passive"))
      (node (ref "R13") (pin "2") (pinfunction "2_2") (pintype "passive"))
    )
    (net (code "62") (name "Net-(Q2-C)") (class "Default")
      (node (ref "Q2") (pin "3") (pinfunction "C_3") (pintype "passive"))
      (node (ref "R7") (pin "2") (pintype "passive"))
    )
    (net (code "63") (name "Net-(Q3-D)") (class "Default")
      (node (ref "C15") (pin "1") (pinfunction "1_1") (pintype "passive"))
      (node (ref "CN1") (pin "2") (pinfunction "2_2") (pintype "passive"))
      (node (ref "Q3") (pin "3") (pinfunction "D_3") (pintype "passive"))
    )
    (net (code "64") (name "Net-(Q3-G)") (class "Default")
      (node (ref "Q3") (pin "1") (pinfunction "G_1") (pintype "passive"))
      (node (ref "R19") (pin "1") (pinfunction "1_1") (pintype "passive"))
      (node (ref "R20") (pin "2") (pinfunction "2_2") (pintype "passive"))
    )
    (net (code "65") (name "Net-(Q4-G)") (class "Default")
      (node (ref "Q4") (pin "1") (pinfunction "G_1") (pintype "passive"))
      (node (ref "R29") (pin "2") (pintype "passive"))
      (node (ref "R32") (pin "1") (pintype "passive"))
    )
    (net (code "66") (name "Net-(Q5-B)") (class "Default")
      (node (ref "Q5") (pin "1") (pinfunction "B_1") (pintype "passive"))
      (node (ref "R33") (pin "1") (pinfunction "1_1") (pintype "passive"))
      (node (ref "R34") (pin "2") (pinfunction "2_2") (pintype "passive"))
    )
    (net (code "67") (name "Net-(Q5-C)") (class "Default")
      (node (ref "Q5") (pin "3") (pinfunction "C_3") (pintype "passive"))
      (node (ref "R32") (pin "2") (pintype "passive"))
    )
    (net (code "68") (name "Net-(Q7-DRAIN)") (class "Default")
      (node (ref "Q7") (pin "3") (pinfunction "DRAIN_3") (pintype "passive"))
      (node (ref "R40") (pin "1") (pinfunction "1_1") (pintype "passive"))
    )
    (net (code "69") (name "Net-(R12-Pad2)") (class "Default")
      (node (ref "R12") (pin "2") (pinfunction "2_2") (pintype "passive"))
      (node (ref "R16") (pin "2") (pinfunction "2_2") (pintype "passive"))
      (node (ref "R17") (pin "1") (pinfunction "1_1") (pintype "passive"))
    )
    (net (code "70") (name "Net-(U1-PROG)") (class "Default")
      (node (ref "R1") (pin "2") (pinfunction "2_2") (pintype "passive"))
      (node (ref "R40") (pin "2") (pinfunction "2_2") (pintype "passive"))
      (node (ref "U1") (pin "2") (pinfunction "PROG_2") (pintype "passive"))
    )
    (net (code "71") (name "Net-(U1-VCC)") (class "Default")
      (node (ref "C6") (pin "2") (pintype "passive"))
      (node (ref "R3") (pin "1") (pinfunction "1_1") (pintype "passive"))
      (node (ref "U1") (pin "4") (pinfunction "VCC_4") (pintype "passive"))
    )
    (net (code "72") (name "Net-(U2-EN)") (class "Default")
      (node (ref "R2") (pin "2") (pinfunction "2_2") (pintype "passive"))
      (node (ref "U2") (pin "3") (pinfunction "EN_3") (pintype "passive"))
    )
    (net (code "73") (name "Net-(U3-VDD1V2)") (class "Default")
      (node (ref "C22") (pin "2") (pintype "passive"))
      (node (ref "U3") (pin "17") (pinfunction "VDD1V2_17") (pintype "passive"))
    )
    (net (code "74") (name "Net-(U4-1B)") (class "Default")
      (node (ref "R21") (pin "1") (pinfunction "1_1") (pintype "passive"))
      (node (ref "U4") (pin "1") (pinfunction "1B_1") (pintype "passive"))
    )
    (net (code "75") (name "Net-(U4-2B)") (class "Default")
      (node (ref "R22") (pin "1") (pinfunction "1_1") (pintype "passive"))
      (node (ref "U4") (pin "2") (pinfunction "2B_2") (pintype "passive"))
    )
    (net (code "76") (name "Net-(U4-3B)") (class "Default")
      (node (ref "R23") (pin "1") (pinfunction "1_1") (pintype "passive"))
      (node (ref "U4") (pin "3") (pinfunction "3B_3") (pintype "passive"))
    )
    (net (code "77") (name "Net-(U4-4B)") (class "Default")
      (node (ref "R24") (pin "1") (pinfunction "1_1") (pintype "passive"))
      (node (ref "U4") (pin "4") (pinfunction "4B_4") (pintype "passive"))
    )
    (net (code "78") (name "Net-(U5-LX)") (class "Default")
      (node (ref "L4") (pin "2") (pinfunction "2_2") (pintype "passive"))
      (node (ref "U5") (pin "2") (pinfunction "LX_2") (pintype "passive"))
    )
    (net (code "79") (name "Net-(U6-1B)") (class "Default")
      (node (ref "R25") (pin "1") (pinfunction "1_1") (pintype "passive"))
      (node (ref "U6") (pin "1") (pinfunction "1B_1") (pintype "passive"))
    )
    (net (code "80") (name "Net-(U6-2B)") (class "Default")
      (node (ref "R26") (pin "1") (pinfunction "1_1") (pintype "passive"))
      (node (ref "U6") (pin "2") (pinfunction "2B_2") (pintype "passive"))
    )
    (net (code "81") (name "Net-(U6-3B)") (class "Default")
      (node (ref "R27") (pin "1") (pinfunction "1_1") (pintype "passive"))
      (node (ref "U6") (pin "3") (pinfunction "3B_3") (pintype "passive"))
    )
    (net (code "82") (name "Net-(U6-4B)") (class "Default")
      (node (ref "R28") (pin "1") (pinfunction "1_1") (pintype "passive"))
      (node (ref "U6") (pin "4") (pinfunction "4B_4") (pintype "passive"))
    )
    (net (code "83") (name "VBUS_BAT") (class "Default")
      (node (ref "C2") (pin "2") (pinfunction "2_2") (pintype "passive"))
      (node (ref "C20") (pin "1") (pinfunction "1_1") (pintype "passive"))
      (node (ref "C21") (pin "2") (pinfunction "2_2") (pintype "passive"))
      (node (ref "D7") (pin "2") (pinfunction "K_2") (pintype "passive"))
      (node (ref "J1") (pin "5") (pinfunction "5_5") (pintype "passive"))
      (node (ref "J2") (pin "5") (pinfunction "5_5") (pintype "passive"))
      (node (ref "Q4") (pin "2") (pinfunction "D_2") (pintype "passive"))
      (node (ref "Q6") (pin "2") (pinfunction "S_2") (pintype "passive"))
      (node (ref "R2") (pin "1") (pinfunction "1_1") (pintype "passive"))
      (node (ref "R29") (pin "1") (pintype "passive"))
      (node (ref "U2") (pin "1") (pinfunction "VIN_1") (pintype "passive"))
      (node (ref "U4") (pin "6") (pinfunction "COM_6") (pintype "passive"))
      (node (ref "U6") (pin "6") (pinfunction "COM_6") (pintype "passive"))
    )
    (net (code "84") (name "VCC_USB") (class "Default")
      (node (ref "C1") (pin "2") (pinfunction "2_2") (pintype "passive"))
      (node (ref "D1") (pin "2") (pinfunction "2_2") (pintype "passive"))
      (node (ref "D7") (pin "1") (pinfunction "A_1") (pintype "passive"))
      (node (ref "Q6") (pin "1") (pinfunction "G_1") (pintype "passive"))
      (node (ref "R3") (pin "2") (pinfunction "2_2") (pintype "passive"))
      (node (ref "R35") (pin "1") (pinfunction "1_1") (pintype "passive"))
      (node (ref "R37") (pin "2") (pinfunction "2_2") (pintype "passive"))
      (node (ref "USB1") (pin "A9") (pinfunction "VBUS_A9") (pintype "passive"))
      (node (ref "USB1") (pin "B9") (pinfunction "VBUS_B9") (pintype "passive"))
    )
    (net (code "85") (name "unconnected-(BAT1-Pad4)") (class "Default")
      (node (ref "BAT1") (pin "4") (pinfunction "4_4") (pintype "passive"))
    )
    (net (code "86") (name "unconnected-(BAT1-Pad5)") (class "Default")
      (node (ref "BAT1") (pin "5") (pinfunction "5_5") (pintype "passive"))
    )
    (net (code "87") (name "unconnected-(CN1-Pad3)") (class "Default")
      (node (ref "CN1") (pin "3") (pinfunction "3_3") (pintype "passive"))
    )
    (net (code "88") (name "unconnected-(CN1-Pad4)") (class "Default")
      (node (ref "CN1") (pin "4") (pinfunction "4_4") (pintype "passive"))
    )
    (net (code "89") (name "unconnected-(CN2-Pad5)") (class "Default")
      (node (ref "CN2") (pin "5") (pinfunction "5_5") (pintype "passive"))
    )
    (net (code "90") (name "unconnected-(CN2-Pad6)") (class "Default")
      (node (ref "CN2") (pin "6") (pinfunction "6_6") (pintype "passive"))
    )
    (net (code "91") (name "unconnected-(J1-Pad6)") (class "Default")
      (node (ref "J1") (pin "6") (pinfunction "6_6") (pintype "passive"))
    )
    (net (code "92") (name "unconnected-(J1-Pad7)") (class "Default")
      (node (ref "J1") (pin "7") (pinfunction "7_7") (pintype "passive"))
    )
    (net (code "93") (name "unconnected-(J2-Pad6)") (class "Default")
      (node (ref "J2") (pin "6") (pinfunction "6_6") (pintype "passive"))
    )
    (net (code "94") (name "unconnected-(J2-Pad7)") (class "Default")
      (node (ref "J2") (pin "7") (pinfunction "7_7") (pintype "passive"))
    )
    (net (code "95") (name "unconnected-(P1-Pad1)") (class "Default")
      (node (ref "P1") (pin "1") (pinfunction "1_1") (pintype "passive"))
    )
    (net (code "96") (name "unconnected-(U1-STDBY-Pad6)") (class "Default")
      (node (ref "U1") (pin "6") (pinfunction "STDBY_6") (pintype "passive"))
    )
    (net (code "97") (name "unconnected-(U2-NC-Pad4)") (class "Default")
      (node (ref "U2") (pin "4") (pinfunction "NC_4") (pintype "passive"))
    )
    (net (code "98") (name "unconnected-(U3-PC[7]-Pad33)") (class "Default")
      (node (ref "U3") (pin "33") (pinfunction "PC[7]_33") (pintype "passive"))
    )
    (net (code "99") (name "unconnected-(U3-PD[0]-Pad36)") (class "Default")
      (node (ref "U3") (pin "36") (pinfunction "PD[0]_36") (pintype "passive"))
    )
    (net (code "100") (name "unconnected-(U3-PD[1]-Pad37)") (class "Default")
      (node (ref "U3") (pin "37") (pinfunction "PD[1]_37") (pintype "passive"))
    )
    (net (code "101") (name "unconnected-(U3-PF[1]-Pad35)") (class "Default")
      (node (ref "U3") (pin "35") (pinfunction "PF[1]_35") (pintype "passive"))
    )
  )
)
